# sensors.net
KiCad netlist of a schematic drawn in EAGLE
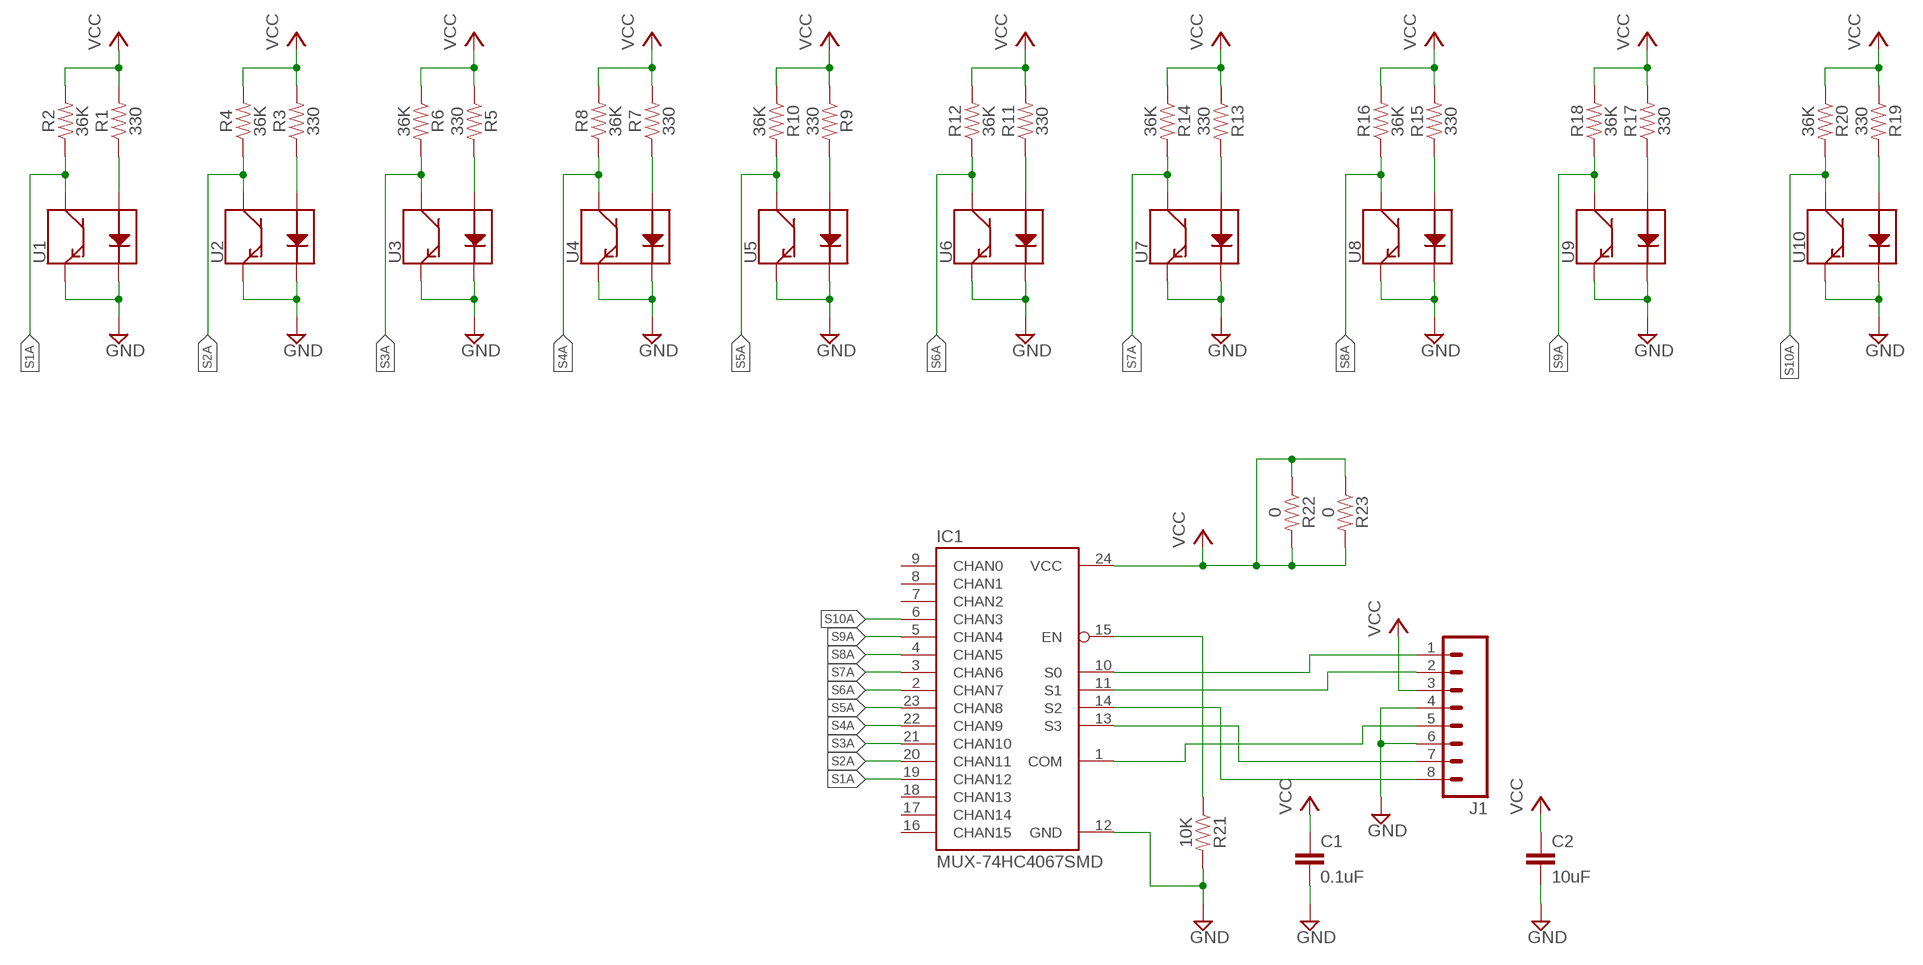
[diagram p0: schematic, sheet 1]

(export (version "E")
  (design (tool "Eeschema 10.0.6"))
  (components
    (comp (ref "C1")
      (value "0.1uF")
      (footprint "eagle-import:0805")
      (libsource (lib "eagle-import") (part "1.0UF-0805-25V-(+80/-20%)"))
    )
    (comp (ref "C2")
      (value "10uF")
      (footprint "eagle-import:0805")
      (libsource (lib "eagle-import") (part "1.0UF-0805-25V-(+80/-20%)"))
    )
    (comp (ref "IC1")
      (value "MUX-74HC4067SMD")
      (footprint "eagle-import:SSOP24")
      (libsource (lib "eagle-import") (part "MUX-74HC4067SMD"))
    )
    (comp (ref "J1")
      (value "M08")
      (footprint "eagle-import:1X08_ROUND")
      (libsource (lib "eagle-import") (part "M08"))
    )
    (comp (ref "R1")
      (value "330")
      (footprint "eagle-import:0805")
      (libsource (lib "eagle-import") (part "RESISTOR0805"))
    )
    (comp (ref "R2")
      (value "36K")
      (footprint "eagle-import:0805")
      (libsource (lib "eagle-import") (part "RESISTOR0805"))
    )
    (comp (ref "R3")
      (value "330")
      (footprint "eagle-import:0805")
      (libsource (lib "eagle-import") (part "RESISTOR0805"))
    )
    (comp (ref "R4")
      (value "36K")
      (footprint "eagle-import:0805")
      (libsource (lib "eagle-import") (part "RESISTOR0805"))
    )
    (comp (ref "R5")
      (value "330")
      (footprint "eagle-import:0805")
      (libsource (lib "eagle-import") (part "RESISTOR0805"))
    )
    (comp (ref "R6")
      (value "36K")
      (footprint "eagle-import:0805")
      (libsource (lib "eagle-import") (part "RESISTOR0805"))
    )
    (comp (ref "R7")
      (value "330")
      (footprint "eagle-import:0805")
      (libsource (lib "eagle-import") (part "RESISTOR0805"))
    )
    (comp (ref "R8")
      (value "36K")
      (footprint "eagle-import:0805")
      (libsource (lib "eagle-import") (part "RESISTOR0805"))
    )
    (comp (ref "R9")
      (value "330")
      (footprint "eagle-import:0805")
      (libsource (lib "eagle-import") (part "RESISTOR0805"))
    )
    (comp (ref "R10")
      (value "36K")
      (footprint "eagle-import:0805")
      (libsource (lib "eagle-import") (part "RESISTOR0805"))
    )
    (comp (ref "R11")
      (value "330")
      (footprint "eagle-import:0805")
      (libsource (lib "eagle-import") (part "RESISTOR0805"))
    )
    (comp (ref "R12")
      (value "36K")
      (footprint "eagle-import:0805")
      (libsource (lib "eagle-import") (part "RESISTOR0805"))
    )
    (comp (ref "R13")
      (value "330")
      (footprint "eagle-import:0805")
      (libsource (lib "eagle-import") (part "RESISTOR0805"))
    )
    (comp (ref "R14")
      (value "36K")
      (footprint "eagle-import:0805")
      (libsource (lib "eagle-import") (part "RESISTOR0805"))
    )
    (comp (ref "R15")
      (value "330")
      (footprint "eagle-import:0805")
      (libsource (lib "eagle-import") (part "RESISTOR0805"))
    )
    (comp (ref "R16")
      (value "36K")
      (footprint "eagle-import:0805")
      (libsource (lib "eagle-import") (part "RESISTOR0805"))
    )
    (comp (ref "R17")
      (value "330")
      (footprint "eagle-import:0805")
      (libsource (lib "eagle-import") (part "RESISTOR0805"))
    )
    (comp (ref "R18")
      (value "36K")
      (footprint "eagle-import:0805")
      (libsource (lib "eagle-import") (part "RESISTOR0805"))
    )
    (comp (ref "R19")
      (value "330")
      (footprint "eagle-import:0805")
      (libsource (lib "eagle-import") (part "RESISTOR0805"))
    )
    (comp (ref "R20")
      (value "36K")
      (footprint "eagle-import:0805")
      (libsource (lib "eagle-import") (part "RESISTOR0805"))
    )
    (comp (ref "R21")
      (value "10K")
      (footprint "eagle-import:0805")
      (libsource (lib "eagle-import") (part "RESISTOR0805"))
    )
    (comp (ref "R22")
      (value "0")
      (footprint "eagle-import:0805")
      (libsource (lib "eagle-import") (part "RESISTOR0805"))
    )
    (comp (ref "R23")
      (value "0")
      (footprint "eagle-import:0805")
      (libsource (lib "eagle-import") (part "RESISTOR0805"))
    )
    (comp (ref "U1")
      (value "QRE1113SMD-W")
      (footprint "eagle-import:QRE1113-W")
      (libsource (lib "eagle-import") (part "QRE1113SMD-W"))
    )
    (comp (ref "U2")
      (value "QRE1113SMD-W")
      (footprint "eagle-import:QRE1113-W")
      (libsource (lib "eagle-import") (part "QRE1113SMD-W"))
    )
    (comp (ref "U3")
      (value "QRE1113SMD-W")
      (footprint "eagle-import:QRE1113-W")
      (libsource (lib "eagle-import") (part "QRE1113SMD-W"))
    )
    (comp (ref "U4")
      (value "QRE1113SMD-W")
      (footprint "eagle-import:QRE1113-W")
      (libsource (lib "eagle-import") (part "QRE1113SMD-W"))
    )
    (comp (ref "U5")
      (value "QRE1113SMD-W")
      (footprint "eagle-import:QRE1113-W")
      (libsource (lib "eagle-import") (part "QRE1113SMD-W"))
    )
    (comp (ref "U6")
      (value "QRE1113SMD-W")
      (footprint "eagle-import:QRE1113-W")
      (libsource (lib "eagle-import") (part "QRE1113SMD-W"))
    )
    (comp (ref "U7")
      (value "QRE1113SMD-W")
      (footprint "eagle-import:QRE1113-W")
      (libsource (lib "eagle-import") (part "QRE1113SMD-W"))
    )
    (comp (ref "U8")
      (value "QRE1113SMD-W")
      (footprint "eagle-import:QRE1113-W")
      (libsource (lib "eagle-import") (part "QRE1113SMD-W"))
    )
    (comp (ref "U9")
      (value "QRE1113SMD-W")
      (footprint "eagle-import:QRE1113-W")
      (libsource (lib "eagle-import") (part "QRE1113SMD-W"))
    )
    (comp (ref "U10")
      (value "QRE1113SMD-W")
      (footprint "eagle-import:QRE1113-W")
      (libsource (lib "eagle-import") (part "QRE1113SMD-W"))
    )
  )
  (nets
    (net (code "1") (name "GND") (class "Default")
      (node (ref "C1") (pin "2") (pinfunction "2_2") (pintype "passive"))
      (node (ref "C2") (pin "2") (pinfunction "2_2") (pintype "passive"))
      (node (ref "IC1") (pin "12") (pinfunction "GND_12") (pintype "bidirectional"))
      (node (ref "J1") (pin "4") (pinfunction "4_4") (pintype "passive"))
      (node (ref "J1") (pin "6") (pinfunction "6_6") (pintype "passive"))
      (node (ref "R21") (pin "2") (pinfunction "2_2") (pintype "passive"))
      (node (ref "U1") (pin "2") (pinfunction "K_2") (pintype "bidirectional"))
      (node (ref "U1") (pin "4") (pinfunction "E_4") (pintype "bidirectional"))
      (node (ref "U10") (pin "2") (pinfunction "K_2") (pintype "bidirectional"))
      (node (ref "U10") (pin "4") (pinfunction "E_4") (pintype "bidirectional"))
      (node (ref "U2") (pin "2") (pinfunction "K_2") (pintype "bidirectional"))
      (node (ref "U2") (pin "4") (pinfunction "E_4") (pintype "bidirectional"))
      (node (ref "U3") (pin "2") (pinfunction "K_2") (pintype "bidirectional"))
      (node (ref "U3") (pin "4") (pinfunction "E_4") (pintype "bidirectional"))
      (node (ref "U4") (pin "2") (pinfunction "K_2") (pintype "bidirectional"))
      (node (ref "U4") (pin "4") (pinfunction "E_4") (pintype "bidirectional"))
      (node (ref "U5") (pin "2") (pinfunction "K_2") (pintype "bidirectional"))
      (node (ref "U5") (pin "4") (pinfunction "E_4") (pintype "bidirectional"))
      (node (ref "U6") (pin "2") (pinfunction "K_2") (pintype "bidirectional"))
      (node (ref "U6") (pin "4") (pinfunction "E_4") (pintype "bidirectional"))
      (node (ref "U7") (pin "2") (pinfunction "K_2") (pintype "bidirectional"))
      (node (ref "U7") (pin "4") (pinfunction "E_4") (pintype "bidirectional"))
      (node (ref "U8") (pin "2") (pinfunction "K_2") (pintype "bidirectional"))
      (node (ref "U8") (pin "4") (pinfunction "E_4") (pintype "bidirectional"))
      (node (ref "U9") (pin "2") (pinfunction "K_2") (pintype "bidirectional"))
      (node (ref "U9") (pin "4") (pinfunction "E_4") (pintype "bidirectional"))
    )
    (net (code "2") (name "Net-(IC1-COM)") (class "Default")
      (node (ref "IC1") (pin "1") (pinfunction "COM_1") (pintype "bidirectional"))
      (node (ref "J1") (pin "5") (pinfunction "5_5") (pintype "passive"))
    )
    (net (code "3") (name "Net-(IC1-EN)") (class "Default")
      (node (ref "IC1") (pin "15") (pinfunction "EN_15") (pintype "input"))
      (node (ref "R21") (pin "1") (pinfunction "1_1") (pintype "passive"))
    )
    (net (code "4") (name "Net-(IC1-S0)") (class "Default")
      (node (ref "IC1") (pin "10") (pinfunction "S0_10") (pintype "input"))
      (node (ref "J1") (pin "1") (pinfunction "1_1") (pintype "passive"))
    )
    (net (code "5") (name "Net-(IC1-S1)") (class "Default")
      (node (ref "IC1") (pin "11") (pinfunction "S1_11") (pintype "input"))
      (node (ref "J1") (pin "2") (pinfunction "2_2") (pintype "passive"))
    )
    (net (code "6") (name "Net-(IC1-S2)") (class "Default")
      (node (ref "IC1") (pin "14") (pinfunction "S2_14") (pintype "input"))
      (node (ref "J1") (pin "8") (pinfunction "8_8") (pintype "passive"))
    )
    (net (code "7") (name "Net-(IC1-S3)") (class "Default")
      (node (ref "IC1") (pin "13") (pinfunction "S3_13") (pintype "input"))
      (node (ref "J1") (pin "7") (pinfunction "7_7") (pintype "passive"))
    )
    (net (code "8") (name "Net-(U1-A)") (class "Default")
      (node (ref "R1") (pin "1") (pinfunction "1_1") (pintype "passive"))
      (node (ref "U1") (pin "1") (pinfunction "A_1") (pintype "bidirectional"))
    )
    (net (code "9") (name "Net-(U2-A)") (class "Default")
      (node (ref "R3") (pin "1") (pinfunction "1_1") (pintype "passive"))
      (node (ref "U2") (pin "1") (pinfunction "A_1") (pintype "bidirectional"))
    )
    (net (code "10") (name "Net-(U3-A)") (class "Default")
      (node (ref "R5") (pin "2") (pinfunction "2_2") (pintype "passive"))
      (node (ref "U3") (pin "1") (pinfunction "A_1") (pintype "bidirectional"))
    )
    (net (code "11") (name "Net-(U4-A)") (class "Default")
      (node (ref "R7") (pin "1") (pinfunction "1_1") (pintype "passive"))
      (node (ref "U4") (pin "1") (pinfunction "A_1") (pintype "bidirectional"))
    )
    (net (code "12") (name "Net-(U5-A)") (class "Default")
      (node (ref "R9") (pin "2") (pinfunction "2_2") (pintype "passive"))
      (node (ref "U5") (pin "1") (pinfunction "A_1") (pintype "bidirectional"))
    )
    (net (code "13") (name "Net-(U6-A)") (class "Default")
      (node (ref "R11") (pin "1") (pinfunction "1_1") (pintype "passive"))
      (node (ref "U6") (pin "1") (pinfunction "A_1") (pintype "bidirectional"))
    )
    (net (code "14") (name "Net-(U7-A)") (class "Default")
      (node (ref "R13") (pin "2") (pinfunction "2_2") (pintype "passive"))
      (node (ref "U7") (pin "1") (pinfunction "A_1") (pintype "bidirectional"))
    )
    (net (code "15") (name "Net-(U8-A)") (class "Default")
      (node (ref "R15") (pin "1") (pinfunction "1_1") (pintype "passive"))
      (node (ref "U8") (pin "1") (pinfunction "A_1") (pintype "bidirectional"))
    )
    (net (code "16") (name "Net-(U9-A)") (class "Default")
      (node (ref "R17") (pin "1") (pinfunction "1_1") (pintype "passive"))
      (node (ref "U9") (pin "1") (pinfunction "A_1") (pintype "bidirectional"))
    )
    (net (code "17") (name "Net-(U10-A)") (class "Default")
      (node (ref "R19") (pin "2") (pinfunction "2_2") (pintype "passive"))
      (node (ref "U10") (pin "1") (pinfunction "A_1") (pintype "bidirectional"))
    )
    (net (code "18") (name "S1A") (class "Default")
      (node (ref "IC1") (pin "19") (pinfunction "CHAN12_19") (pintype "bidirectional"))
      (node (ref "R2") (pin "1") (pinfunction "1_1") (pintype "passive"))
      (node (ref "U1") (pin "3") (pinfunction "C_3") (pintype "bidirectional"))
    )
    (net (code "19") (name "S2A") (class "Default")
      (node (ref "IC1") (pin "20") (pinfunction "CHAN11_20") (pintype "bidirectional"))
      (node (ref "R4") (pin "1") (pinfunction "1_1") (pintype "passive"))
      (node (ref "U2") (pin "3") (pinfunction "C_3") (pintype "bidirectional"))
    )
    (net (code "20") (name "S3A") (class "Default")
      (node (ref "IC1") (pin "21") (pinfunction "CHAN10_21") (pintype "bidirectional"))
      (node (ref "R6") (pin "2") (pinfunction "2_2") (pintype "passive"))
      (node (ref "U3") (pin "3") (pinfunction "C_3") (pintype "bidirectional"))
    )
    (net (code "21") (name "S4A") (class "Default")
      (node (ref "IC1") (pin "22") (pinfunction "CHAN9_22") (pintype "bidirectional"))
      (node (ref "R8") (pin "1") (pinfunction "1_1") (pintype "passive"))
      (node (ref "U4") (pin "3") (pinfunction "C_3") (pintype "bidirectional"))
    )
    (net (code "22") (name "S5A") (class "Default")
      (node (ref "IC1") (pin "23") (pinfunction "CHAN8_23") (pintype "bidirectional"))
      (node (ref "R10") (pin "2") (pinfunction "2_2") (pintype "passive"))
      (node (ref "U5") (pin "3") (pinfunction "C_3") (pintype "bidirectional"))
    )
    (net (code "23") (name "S6A") (class "Default")
      (node (ref "IC1") (pin "2") (pinfunction "CHAN7_2") (pintype "bidirectional"))
      (node (ref "R12") (pin "1") (pinfunction "1_1") (pintype "passive"))
      (node (ref "U6") (pin "3") (pinfunction "C_3") (pintype "bidirectional"))
    )
    (net (code "24") (name "S7A") (class "Default")
      (node (ref "IC1") (pin "3") (pinfunction "CHAN6_3") (pintype "bidirectional"))
      (node (ref "R14") (pin "2") (pinfunction "2_2") (pintype "passive"))
      (node (ref "U7") (pin "3") (pinfunction "C_3") (pintype "bidirectional"))
    )
    (net (code "25") (name "S8A") (class "Default")
      (node (ref "IC1") (pin "4") (pinfunction "CHAN5_4") (pintype "bidirectional"))
      (node (ref "R16") (pin "1") (pinfunction "1_1") (pintype "passive"))
      (node (ref "U8") (pin "3") (pinfunction "C_3") (pintype "bidirectional"))
    )
    (net (code "26") (name "S9A") (class "Default")
      (node (ref "IC1") (pin "5") (pinfunction "CHAN4_5") (pintype "bidirectional"))
      (node (ref "R18") (pin "1") (pinfunction "1_1") (pintype "passive"))
      (node (ref "U9") (pin "3") (pinfunction "C_3") (pintype "bidirectional"))
    )
    (net (code "27") (name "S10A") (class "Default")
      (node (ref "IC1") (pin "6") (pinfunction "CHAN3_6") (pintype "bidirectional"))
      (node (ref "R20") (pin "2") (pinfunction "2_2") (pintype "passive"))
      (node (ref "U10") (pin "3") (pinfunction "C_3") (pintype "bidirectional"))
    )
    (net (code "28") (name "VCC") (class "Default")
      (node (ref "C1") (pin "1") (pinfunction "1_1") (pintype "passive"))
      (node (ref "C2") (pin "1") (pinfunction "1_1") (pintype "passive"))
      (node (ref "IC1") (pin "24") (pinfunction "VCC_24") (pintype "bidirectional"))
      (node (ref "J1") (pin "3") (pinfunction "3_3") (pintype "passive"))
      (node (ref "R1") (pin "2") (pinfunction "2_2") (pintype "passive"))
      (node (ref "R10") (pin "1") (pinfunction "1_1") (pintype "passive"))
      (node (ref "R11") (pin "2") (pinfunction "2_2") (pintype "passive"))
      (node (ref "R12") (pin "2") (pinfunction "2_2") (pintype "passive"))
      (node (ref "R13") (pin "1") (pinfunction "1_1") (pintype "passive"))
      (node (ref "R14") (pin "1") (pinfunction "1_1") (pintype "passive"))
      (node (ref "R15") (pin "2") (pinfunction "2_2") (pintype "passive"))
      (node (ref "R16") (pin "2") (pinfunction "2_2") (pintype "passive"))
      (node (ref "R17") (pin "2") (pinfunction "2_2") (pintype "passive"))
      (node (ref "R18") (pin "2") (pinfunction "2_2") (pintype "passive"))
      (node (ref "R19") (pin "1") (pinfunction "1_1") (pintype "passive"))
      (node (ref "R2") (pin "2") (pinfunction "2_2") (pintype "passive"))
      (node (ref "R20") (pin "1") (pinfunction "1_1") (pintype "passive"))
      (node (ref "R22") (pin "1") (pinfunction "1_1") (pintype "passive"))
      (node (ref "R22") (pin "2") (pinfunction "2_2") (pintype "passive"))
      (node (ref "R23") (pin "1") (pinfunction "1_1") (pintype "passive"))
      (node (ref "R23") (pin "2") (pinfunction "2_2") (pintype "passive"))
      (node (ref "R3") (pin "2") (pinfunction "2_2") (pintype "passive"))
      (node (ref "R4") (pin "2") (pinfunction "2_2") (pintype "passive"))
      (node (ref "R5") (pin "1") (pinfunction "1_1") (pintype "passive"))
      (node (ref "R6") (pin "1") (pinfunction "1_1") (pintype "passive"))
      (node (ref "R7") (pin "2") (pinfunction "2_2") (pintype "passive"))
      (node (ref "R8") (pin "2") (pinfunction "2_2") (pintype "passive"))
      (node (ref "R9") (pin "1") (pinfunction "1_1") (pintype "passive"))
    )
    (net (code "29") (name "unconnected-(IC1-CHAN0-Pad9)") (class "Default")
      (node (ref "IC1") (pin "9") (pinfunction "CHAN0_9") (pintype "bidirectional"))
    )
    (net (code "30") (name "unconnected-(IC1-CHAN1-Pad8)") (class "Default")
      (node (ref "IC1") (pin "8") (pinfunction "CHAN1_8") (pintype "bidirectional"))
    )
    (net (code "31") (name "unconnected-(IC1-CHAN2-Pad7)") (class "Default")
      (node (ref "IC1") (pin "7") (pinfunction "CHAN2_7") (pintype "bidirectional"))
    )
    (net (code "32") (name "unconnected-(IC1-CHAN13-Pad18)") (class "Default")
      (node (ref "IC1") (pin "18") (pinfunction "CHAN13_18") (pintype "bidirectional"))
    )
    (net (code "33") (name "unconnected-(IC1-CHAN14-Pad17)") (class "Default")
      (node (ref "IC1") (pin "17") (pinfunction "CHAN14_17") (pintype "bidirectional"))
    )
    (net (code "34") (name "unconnected-(IC1-CHAN15-Pad16)") (class "Default")
      (node (ref "IC1") (pin "16") (pinfunction "CHAN15_16") (pintype "bidirectional"))
    )
  )
)
